# H0FR7.net
KiCad netlist of a schematic drawn in EAGLE
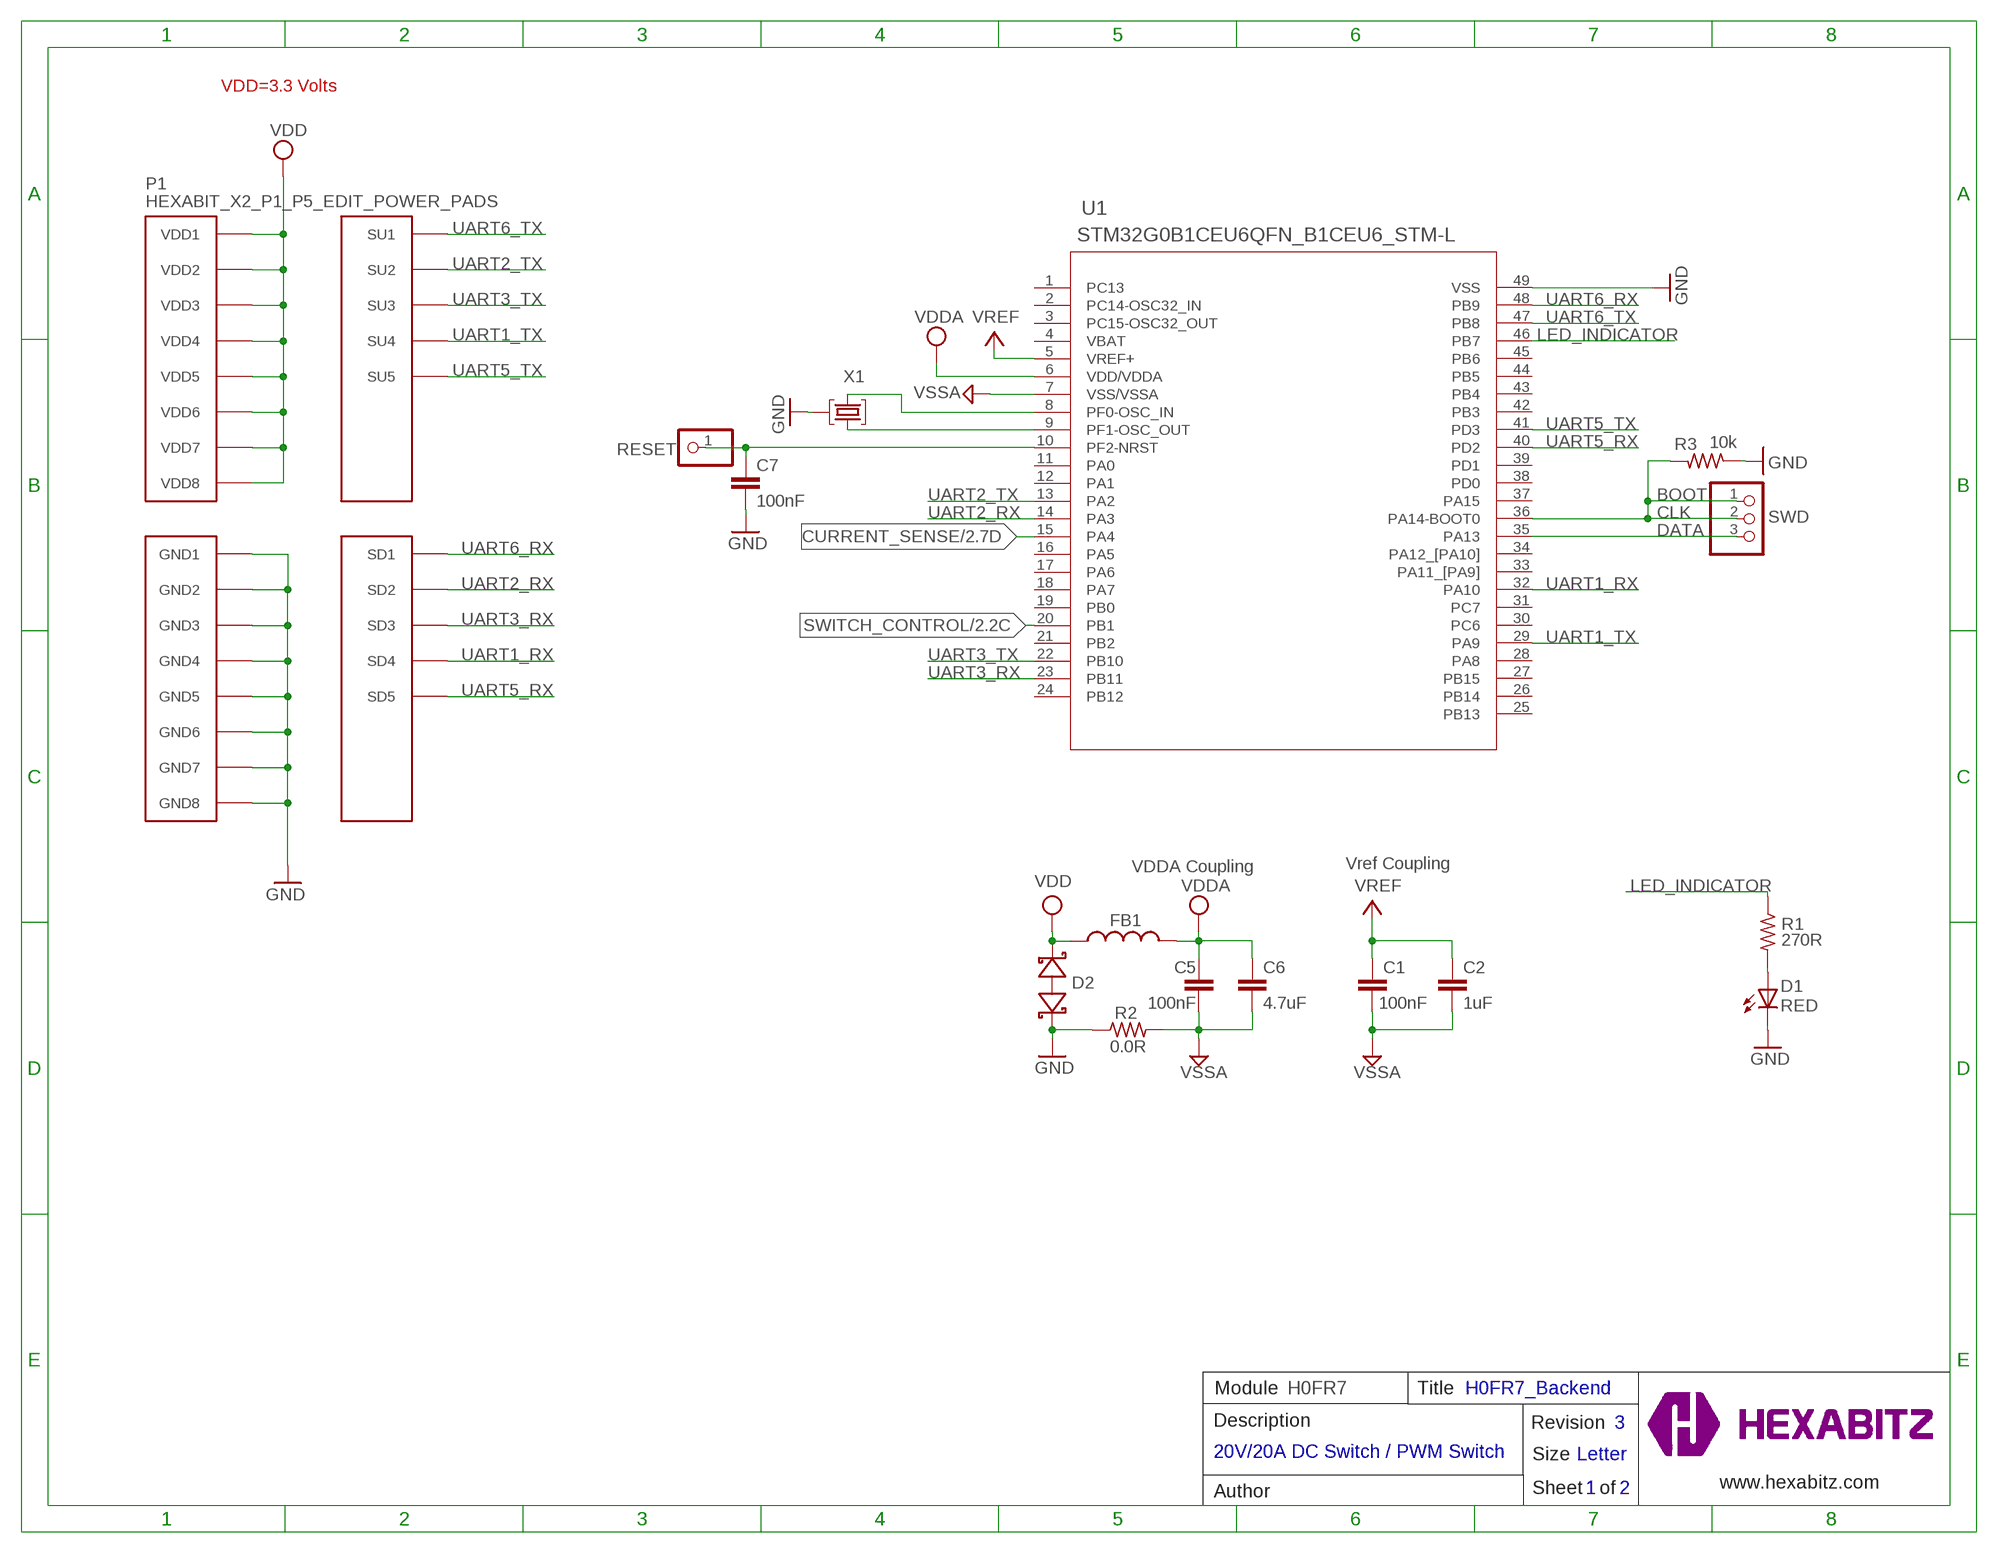
[diagram p0: schematic, sheet 1]
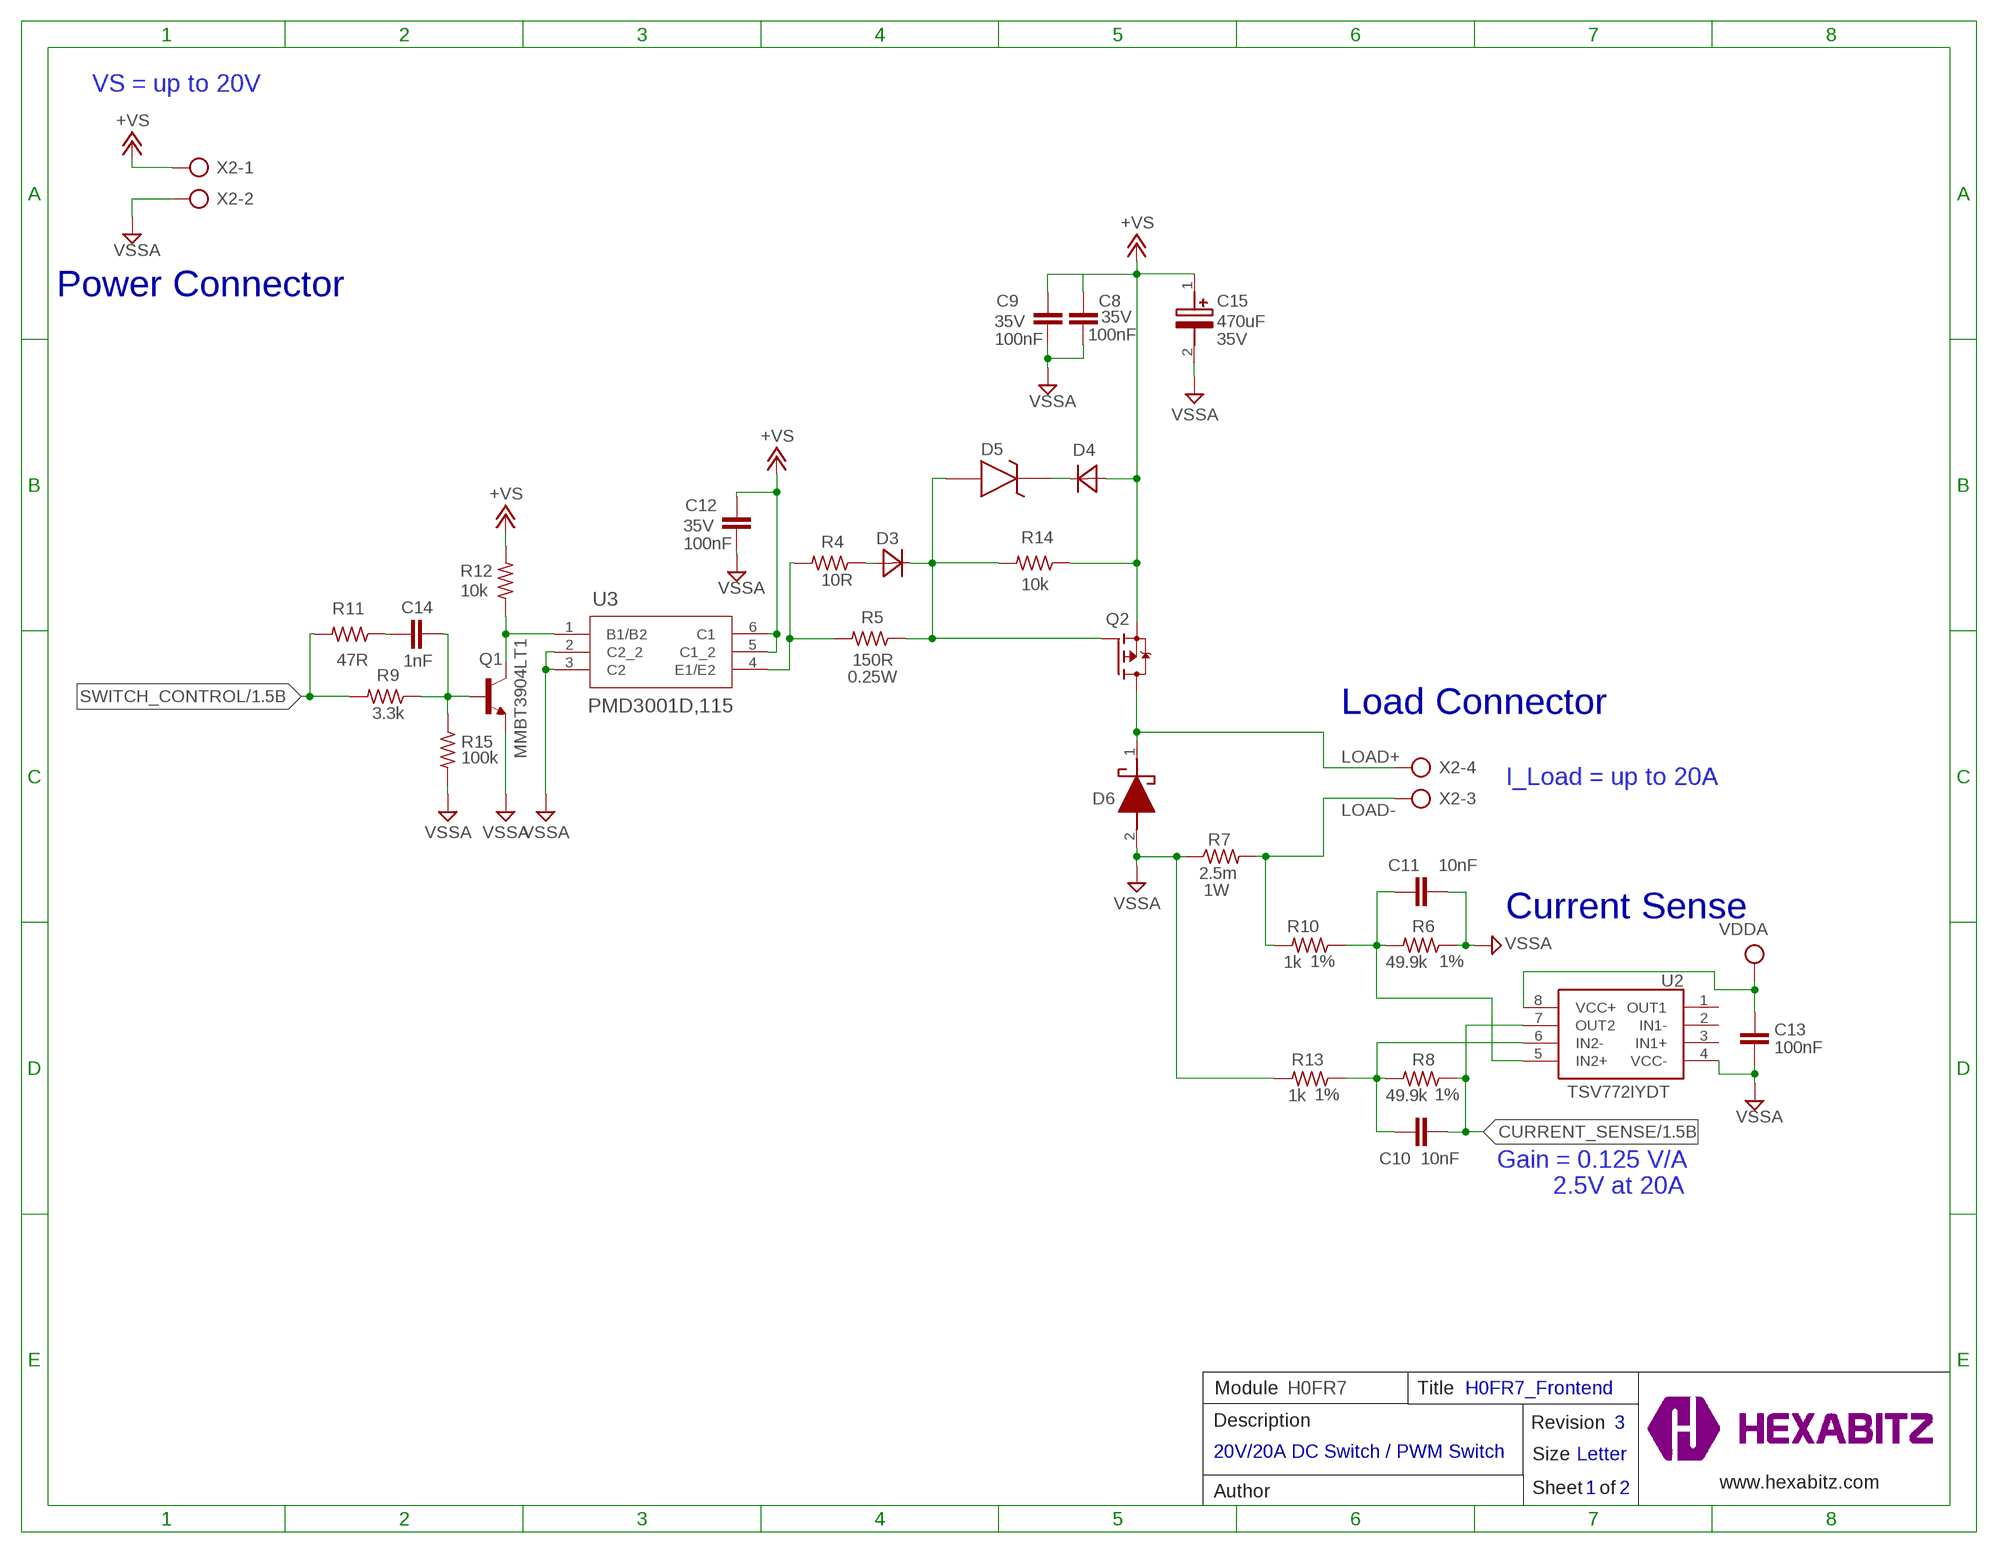
[diagram p1: schematic, sheet 2]

(export (version "E")
  (design (tool "Eeschema 10.0.6"))
  (components
    (comp (ref "C8")
      (value "C-0603")
      (footprint "eagle-import:C-0603")
      (fields (field (name "CAPACITANCE") "100nF") (field (name "VOLTAGE_RATING") "35V"))
      (libsource (lib "eagle-import") (part "C-0603"))
    )
    (comp (ref "C9")
      (value "C-0603")
      (footprint "eagle-import:C-0603")
      (fields (field (name "CAPACITANCE") "100nF") (field (name "VOLTAGE_RATING") "35V"))
      (libsource (lib "eagle-import") (part "C-0603"))
    )
    (comp (ref "C10")
      (value "10nF")
      (footprint "eagle-import:C-0603")
      (fields
        (field (name "CAPACITANCE") "100nF")
        (field (name "MFN") "KEMET")
        (field (name "MPN") "C0603C104K8RACTU")
        (field (name "OCTOPART_URL") "https://octopart.com/c0603c104k8ractu-kemet-145075?r=sp&s=9bS9ASSwSEqMCE9KBEQZ0g")
        (field (name "TOLERANCE") "10V")
        (field (name "VOLTAGE_RATING") "10%")
      )
      (libsource (lib "eagle-import") (part "C-0603"))
    )
    (comp (ref "C11")
      (value "10nF")
      (footprint "eagle-import:C-0603")
      (fields
        (field (name "CAPACITANCE") "100nF")
        (field (name "MFN") "KEMET")
        (field (name "MPN") "C0603C104K8RACTU")
        (field (name "OCTOPART_URL") "https://octopart.com/c0603c104k8ractu-kemet-145075?r=sp&s=9bS9ASSwSEqMCE9KBEQZ0g")
        (field (name "TOLERANCE") "10V")
        (field (name "VOLTAGE_RATING") "10%")
      )
      (libsource (lib "eagle-import") (part "C-0603"))
    )
    (comp (ref "C12")
      (value "C-0603")
      (footprint "eagle-import:C-0603")
      (fields (field (name "CAPACITANCE") "100nF") (field (name "VOLTAGE_RATING") "35V"))
      (libsource (lib "eagle-import") (part "C-0603"))
    )
    (comp (ref "C13")
      (value "100nF")
      (footprint "eagle-import:C-0603")
      (fields
        (field (name "CAPACITANCE") "100nF")
        (field (name "MFN") "KEMET")
        (field (name "MPN") "C0603C104K8RACTU")
        (field (name "OCTOPART_URL") "https://octopart.com/c0603c104k8ractu-kemet-145075?r=sp&s=9bS9ASSwSEqMCE9KBEQZ0g")
        (field (name "TOLERANCE") "10V")
        (field (name "VOLTAGE_RATING") "10%")
      )
      (libsource (lib "eagle-import") (part "C-0603"))
    )
    (comp (ref "C14")
      (value "1nF")
      (footprint "eagle-import:C-0603")
      (fields
        (field (name "CAPACITANCE") "100nF")
        (field (name "MFN") "KEMET")
        (field (name "MPN") "C0603C104K8RACTU")
        (field (name "OCTOPART_URL") "https://octopart.com/c0603c104k8ractu-kemet-145075?r=sp&s=9bS9ASSwSEqMCE9KBEQZ0g")
        (field (name "TOLERANCE") "10%")
        (field (name "VOLTAGE_RATING") "10V")
      )
      (libsource (lib "eagle-import") (part "C-0603"))
    )
    (comp (ref "C15")
      (value "ESH477M035AH3AA")
      (footprint "eagle-import:CAPPRD500W60D1000H1700")
      (fields
        (field (name "MOUSER_PART_NUMBER") "80-ESH477M035AH3AA")
        (field (name "CAPACITANCE") "470uF")
        (field (name "VOLT_RATING") "35V")
      )
      (libsource (lib "eagle-import") (part "ESH477M035AH3AA"))
    )
    (comp (ref "D3")
      (value "DIOD-SOD-123")
      (footprint "eagle-import:SOD123")
      (fields (field (name "MPN") "1N4148W-7-F"))
      (libsource (lib "eagle-import") (part "DIOD-SOD-123"))
    )
    (comp (ref "D4")
      (value "DIOD-SOD-123")
      (footprint "eagle-import:SOD123")
      (fields (field (name "MPN") "1N4148W-7-F"))
      (libsource (lib "eagle-import") (part "DIOD-SOD-123"))
    )
    (comp (ref "D5")
      (value "MMSZ4705T1GMMSZ4705T1G")
      (footprint "eagle-import:DIO_MMSZ4700T1G")
      (fields (field (name "MPN") "MMSZ4678T1G") (field (name "VOLTAGE") "18V"))
      (libsource (lib "eagle-import") (part "MMSZ4705T1GMMSZ4705T1G"))
    )
    (comp (ref "D6")
      (value "V8PAM10S-M3_H")
      (footprint "eagle-import:V8PAM10SHM3H")
      (fields
        (field (name "MANUFACTURER_PART_NUMBER") "V8PAM10S-M3/H")
        (field (name "MOUSER_PART_NUMBER") "78-V8PAM10S-M3/H")
      )
      (libsource (lib "eagle-import") (part "V8PAM10S-M3_H"))
    )
    (comp (ref "Q1")
      (value "MMBT3904LT1")
      (footprint "eagle-import:MMBT3904LT1")
      (libsource (lib "eagle-import") (part "MMBT3904LT1"))
    )
    (comp (ref "Q2")
      (value "STD36P4LLF6")
      (footprint "eagle-import:DPAK-3")
      (libsource (lib "eagle-import") (part "STD36P4LLF6"))
    )
    (comp (ref "R4")
      (value "10R")
      (footprint "eagle-import:R-0603")
      (fields
        (field (name "MFN") "Yageo")
        (field (name "MPN") "RC0603JR-07680KL")
        (field (name "OCTOPART_URL") "https://octopart.com/rc0603jr-07680kl-yageo-40953169?r=sp")
        (field (name "RESISTANCE") "680K Ohm")
        (field (name "TOLERANCE") "5%")
      )
      (libsource (lib "eagle-import") (part "R-0603"))
    )
    (comp (ref "R5")
      (value "150R")
      (footprint "eagle-import:R-0603")
      (fields (field (name "MPN") "CRGP0603F150R") (field (name "POWER") "0.25W"))
      (libsource (lib "eagle-import") (part "R-0603"))
    )
    (comp (ref "R6")
      (value "49.9k")
      (footprint "eagle-import:R-0603")
      (fields
        (field (name "MFN") "Yageo")
        (field (name "MPN") "RC0603JR-071KL")
        (field (name "OCTOPART_URL") "https://octopart.com/rc0603jr-071kl-yageo-55402888?r=sp")
        (field (name "RESISTANCE") "1k")
        (field (name "TOLERANCE") "1%")
      )
      (libsource (lib "eagle-import") (part "R-0603"))
    )
    (comp (ref "R7")
      (value "2.5m")
      (footprint "eagle-import:R1206")
      (fields
        (field (name "MPN") "RNCF2512BTE1M10")
        (field (name "MPN_1") "PA1206FRE472U5Z")
        (field (name "POWER") "1W")
      )
      (libsource (lib "eagle-import") (part "R_1206R1206"))
    )
    (comp (ref "R8")
      (value "49.9k")
      (footprint "eagle-import:R-0603")
      (fields
        (field (name "MFN") "Yageo")
        (field (name "MPN") "RC0603JR-071KL")
        (field (name "OCTOPART_URL") "https://octopart.com/rc0603jr-071kl-yageo-55402888?r=sp")
        (field (name "RESISTANCE") "1k")
        (field (name "TOLERANCE") "1%")
      )
      (libsource (lib "eagle-import") (part "R-0603"))
    )
    (comp (ref "R9")
      (value "3.3k")
      (footprint "eagle-import:R-0603")
      (fields
        (field (name "MFN") "Yageo")
        (field (name "MPN") "RC0603JR-07680KL")
        (field (name "OCTOPART_URL") "https://octopart.com/rc0603jr-07680kl-yageo-40953169?r=sp")
        (field (name "RESISTANCE") "680K Ohm")
        (field (name "TOLERANCE") "5%")
      )
      (libsource (lib "eagle-import") (part "R-0603"))
    )
    (comp (ref "R10")
      (value "1k")
      (footprint "eagle-import:R-0603")
      (fields
        (field (name "MFN") "Yageo")
        (field (name "MPN") "RC0603JR-071KL")
        (field (name "OCTOPART_URL") "https://octopart.com/rc0603jr-071kl-yageo-55402888?r=sp")
        (field (name "RESISTANCE") "1k")
        (field (name "TOLERANCE") "1%")
      )
      (libsource (lib "eagle-import") (part "R-0603"))
    )
    (comp (ref "R11")
      (value "47R")
      (footprint "eagle-import:R-0603")
      (fields
        (field (name "MFN") "Yageo")
        (field (name "MPN") "RC0603JR-07680KL")
        (field (name "OCTOPART_URL") "https://octopart.com/rc0603jr-07680kl-yageo-40953169?r=sp")
        (field (name "RESISTANCE") "680K Ohm")
        (field (name "TOLERANCE") "5%")
      )
      (libsource (lib "eagle-import") (part "R-0603"))
    )
    (comp (ref "R12")
      (value "10k")
      (footprint "eagle-import:R-0603")
      (fields
        (field (name "MFN") "Yageo")
        (field (name "MPN") "RC0603JR-0710KL")
        (field (name "OCTOPART_URL") "https://octopart.com/search?q=RC0603JR-0710KL&start=0")
        (field (name "RESISTANCE") "10.0K Ohm")
        (field (name "TOLERANCE") "5%")
      )
      (libsource (lib "eagle-import") (part "R-0603"))
    )
    (comp (ref "R13")
      (value "1k")
      (footprint "eagle-import:R-0603")
      (fields
        (field (name "MFN") "Yageo")
        (field (name "MPN") "RC0603JR-071KL")
        (field (name "OCTOPART_URL") "https://octopart.com/rc0603jr-071kl-yageo-55402888?r=sp")
        (field (name "RESISTANCE") "1k")
        (field (name "TOLERANCE") "1%")
      )
      (libsource (lib "eagle-import") (part "R-0603"))
    )
    (comp (ref "R14")
      (value "10k")
      (footprint "eagle-import:R-0603")
      (fields
        (field (name "MFN") "Yageo")
        (field (name "MPN") "RC0603JR-07680KL")
        (field (name "OCTOPART_URL") "https://octopart.com/rc0603jr-07680kl-yageo-40953169?r=sp")
        (field (name "RESISTANCE") "680K Ohm")
        (field (name "TOLERANCE") "5%")
      )
      (libsource (lib "eagle-import") (part "R-0603"))
    )
    (comp (ref "R15")
      (value "100k")
      (footprint "eagle-import:R-0603")
      (fields
        (field (name "MFN") "Yageo")
        (field (name "MPN") "RC0603JR-07680KL")
        (field (name "OCTOPART_URL") "https://octopart.com/rc0603jr-07680kl-yageo-40953169?r=sp")
        (field (name "RESISTANCE") "680K Ohm")
        (field (name "TOLERANCE") "5%")
      )
      (libsource (lib "eagle-import") (part "R-0603"))
    )
    (comp (ref "U2")
      (value "TSV772IYDT")
      (footprint "eagle-import:SOIC127P600X175-8N")
      (libsource (lib "eagle-import") (part "TSV772IYDT"))
    )
    (comp (ref "U3")
      (value "PMD3001D,115")
      (footprint "eagle-import:SOT457_NEX")
      (fields
        (field (name "MANUFACTURER_PART_NUMBER") "PMD3001D")
        (field (name "COPYRIGHT") "Copyright (C) 2022 Ultra Librarian. All rights reserved.")
      )
      (libsource (lib "eagle-import") (part "PMD3001DSOT457_NEX"))
    )
    (comp (ref "X2")
      (value "AK300/4")
      (footprint "eagle-import:AK300_4")
      (libsource (lib "eagle-import") (part "AK300/4"))
    )
    (comp (ref "C1")
      (value "100nF")
      (footprint "eagle-import:C-0603")
      (fields
        (field (name "CAPACITANCE") "100nF")
        (field (name "MFN") "KEMET")
        (field (name "MPN") "C0603C104K8RACTU")
        (field (name "OCTOPART_URL") "https://octopart.com/c0603c104k8ractu-kemet-145075?r=sp&s=9bS9ASSwSEqMCE9KBEQZ0g")
        (field (name "TOLERANCE") "10%")
        (field (name "VOLTAGE_RATING") "10V")
      )
      (libsource (lib "eagle-import") (part "C-0603"))
    )
    (comp (ref "C2")
      (value "1uF")
      (footprint "eagle-import:C-0805")
      (libsource (lib "eagle-import") (part "C-0805"))
    )
    (comp (ref "C5")
      (value "100nF")
      (footprint "eagle-import:C-0603")
      (libsource (lib "eagle-import") (part "C-0603"))
    )
    (comp (ref "C6")
      (value "4.7uF")
      (footprint "eagle-import:C-0805")
      (libsource (lib "eagle-import") (part "C-0805"))
    )
    (comp (ref "C7")
      (value "100nF")
      (footprint "eagle-import:C-0603")
      (fields
        (field (name "CAPACITANCE") "100nF")
        (field (name "MFN") "KEMET")
        (field (name "MPN") "C0603C104K8RACTU")
        (field (name "OCTOPART_URL") "https://octopart.com/c0603c104k8ractu-kemet-145075?r=sp&s=9bS9ASSwSEqMCE9KBEQZ0g")
        (field (name "TOLERANCE") "10%")
        (field (name "VOLTAGE_RATING") "10V")
      )
      (libsource (lib "eagle-import") (part "C-0603"))
    )
    (comp (ref "D1")
      (value "RED")
      (footprint "eagle-import:VLMS1300-GS08")
      (fields
        (field (name "MPN") "VLMS1300-GS08")
        (field (name "MFN") "Vishay")
        (field (name "MPN_1") "VLMS1300-GS08")
        (field (name "OCTOPART_URL") "https://octopart.com/vlms1300-gs08-vishay-21709201?r=sp&s=_gcP4_q8T1SC6PJQPTQ9yA")
      )
      (libsource (lib "eagle-import") (part "VLMS1300-GS08"))
    )
    (comp (ref "D2")
      (value "BOURNS_CDSOD323-T03SCBOURNS_CDSOD323-T03SC_0_0")
      (footprint "eagle-import:BOURNS_CDSOD323-T03SC_0")
      (fields (field (name "MPN") "CDSOD323-T03SC"))
      (libsource (lib "eagle-import") (part "BOURNS_CDSOD323-T03SCBOURNS_CDSOD323-T03SC_0_0"))
    )
    (comp (ref "FB1")
      (value "FB-0603")
      (footprint "eagle-import:FB-0603")
      (libsource (lib "eagle-import") (part "FB-0603"))
    )
    (comp (ref "P1")
      (value "HEXABIT_X2_P1_P5_EDIT_POWER_PADS")
      (footprint "eagle-import:HEXABIT_X2_P1_P5_EDIT_POWER_PADS")
      (libsource (lib "eagle-import") (part "HEXABIT_X2_P1_P5_EDIT_POWER_PADS"))
    )
    (comp (ref "R1")
      (value "270R")
      (footprint "eagle-import:R-0603")
      (libsource (lib "eagle-import") (part "R-0603"))
    )
    (comp (ref "R2")
      (value "0.0R")
      (footprint "eagle-import:R-0603")
      (libsource (lib "eagle-import") (part "R-0603"))
    )
    (comp (ref "R3")
      (value "10k")
      (footprint "eagle-import:R-0603")
      (fields
        (field (name "MFN") "Yageo")
        (field (name "MPN") "RC0603JR-0710KL")
        (field (name "OCTOPART_URL") "https://octopart.com/search?q=RC0603JR-0710KL&start=0")
        (field (name "RESISTANCE") "10.0K Ohm")
        (field (name "TOLERANCE") "5%")
      )
      (libsource (lib "eagle-import") (part "R-0603"))
    )
    (comp (ref "RESET")
      (value "R")
      (footprint "eagle-import:1X01")
      (fields (field (name "MPN") "87227-1"))
      (libsource (lib "eagle-import") (part "PINHD-1X1"))
    )
    (comp (ref "SWD")
      (value "PINHD-1X3SWD")
      (footprint "eagle-import:SWD")
      (libsource (lib "eagle-import") (part "PINHD-1X3SWD"))
    )
    (comp (ref "TRIMBLE-LOGO2")
      (value "HEXA-LOGO")
      (footprint "eagle-import:HEXA-LOGO")
      (libsource (lib "eagle-import") (part "HEXA-LOGO"))
    )
    (comp (ref "U1")
      (value "STM32G0B1CEU6QFN_B1CEU6_STM-L")
      (footprint "eagle-import:QFN_B1CEU6_STM-L")
      (fields
        (field (name "MANUFACTURER_PART_NUMBER") "STM32G0B1CEU6")
        (field (name "COPYRIGHT") "Copyright (C) 2021 Ultra Librarian. All rights reserved.")
      )
      (libsource (lib "eagle-import") (part "STM32G0B1CEU6QFN_B1CEU6_STM-L"))
    )
    (comp (ref "X1")
      (value "XTALL_CSTCE8M00G52")
      (footprint "eagle-import:XTALL_CSTCE8M00G52")
      (fields (field (name "MPN") "CSTCE8M00G52Z-R0"))
      (libsource (lib "eagle-import") (part "XTALL_CSTCE8M00G52"))
    )
  )
  (nets
    (net (code "1") (name "+VS") (class "Default")
      (node (ref "C12") (pin "2") (pinfunction "2_2") (pintype "passive"))
      (node (ref "C15") (pin "1") (pinfunction "+_1") (pintype "bidirectional"))
      (node (ref "C8") (pin "2") (pinfunction "2_2") (pintype "passive"))
      (node (ref "C9") (pin "2") (pinfunction "2_2") (pintype "passive"))
      (node (ref "D4") (pin "1") (pinfunction "A_1") (pintype "passive"))
      (node (ref "Q2") (pin "3") (pinfunction "S_3") (pintype "passive"))
      (node (ref "R12") (pin "2") (pinfunction "2_2") (pintype "passive"))
      (node (ref "R14") (pin "1") (pinfunction "1_1") (pintype "passive"))
      (node (ref "U3") (pin "5") (pinfunction "C1_2_5") (pintype "passive"))
      (node (ref "U3") (pin "6") (pinfunction "C1_6") (pintype "passive"))
      (node (ref "X2") (pin "1") (pinfunction "KL_1") (pintype "passive"))
    )
    (net (code "2") (name "CLK") (class "Default")
      (node (ref "R3") (pin "2") (pinfunction "2_2") (pintype "passive"))
      (node (ref "SWD") (pin "1") (pinfunction "1_1") (pintype "passive"))
      (node (ref "SWD") (pin "2") (pinfunction "2_2") (pintype "passive"))
      (node (ref "U1") (pin "36") (pinfunction "PA14-BOOT0_36") (pintype "bidirectional"))
    )
    (net (code "3") (name "CURRENT_SENSE") (class "Default")
      (node (ref "C10") (pin "2") (pinfunction "2_2") (pintype "passive"))
      (node (ref "R8") (pin "1") (pinfunction "1_1") (pintype "passive"))
      (node (ref "U1") (pin "15") (pinfunction "PA4_15") (pintype "bidirectional"))
      (node (ref "U2") (pin "7") (pinfunction "OUT2_7") (pintype "bidirectional"))
    )
    (net (code "4") (name "DATA") (class "Default")
      (node (ref "SWD") (pin "3") (pinfunction "3_3") (pintype "passive"))
      (node (ref "U1") (pin "35") (pinfunction "PA13_35") (pintype "bidirectional"))
    )
    (net (code "5") (name "GND") (class "Default")
      (node (ref "C7") (pin "2") (pinfunction "2_2") (pintype "passive"))
      (node (ref "D1") (pin "C") (pinfunction "C_C") (pintype "passive"))
      (node (ref "D2") (pin "2") (pinfunction "C_2") (pintype "passive"))
      (node (ref "P1") (pin "PAD_PD11") (pinfunction "GND1_PAD_PD11") (pintype "power_in"))
      (node (ref "P1") (pin "PAD_PD12") (pinfunction "GND2_PAD_PD12") (pintype "power_in"))
      (node (ref "P1") (pin "PAD_PD13") (pinfunction "GND3_PAD_PD13") (pintype "power_in"))
      (node (ref "P1") (pin "PAD_PD14") (pinfunction "GND4_PAD_PD14") (pintype "power_in"))
      (node (ref "P1") (pin "PAD_PD17") (pinfunction "GND5_PAD_PD17") (pintype "power_in"))
      (node (ref "P1") (pin "PAD_PD18") (pinfunction "GND6_PAD_PD18") (pintype "power_in"))
      (node (ref "P1") (pin "PAD_PD19") (pinfunction "GND7_PAD_PD19") (pintype "power_in"))
      (node (ref "P1") (pin "PAD_PD20") (pinfunction "GND8_PAD_PD20") (pintype "power_in"))
      (node (ref "R2") (pin "1") (pinfunction "1_1") (pintype "passive"))
      (node (ref "R3") (pin "1") (pinfunction "1_1") (pintype "passive"))
      (node (ref "U1") (pin "49") (pinfunction "VSS_49") (pintype "passive"))
      (node (ref "X1") (pin "P$2") (pinfunction "2_P$2") (pintype "passive"))
    )
    (net (code "6") (name "LED_INDICATOR") (class "Default")
      (node (ref "R1") (pin "1") (pinfunction "1_1") (pintype "passive"))
      (node (ref "U1") (pin "46") (pinfunction "PB7_46") (pintype "bidirectional"))
    )
    (net (code "7") (name "LOAD+") (class "Default")
      (node (ref "D6") (pin "1") (pinfunction "K_1") (pintype "bidirectional"))
      (node (ref "Q2") (pin "4") (pinfunction "D_4") (pintype "passive"))
      (node (ref "X2") (pin "4") (pinfunction "KL_4") (pintype "passive"))
    )
    (net (code "8") (name "LOAD-") (class "Default")
      (node (ref "R10") (pin "2") (pinfunction "2_2") (pintype "passive"))
      (node (ref "R7") (pin "2") (pinfunction "2_2") (pintype "passive"))
      (node (ref "X2") (pin "3") (pinfunction "KL_3") (pintype "passive"))
    )
    (net (code "9") (name "Net-(C14-Pad1)") (class "Default")
      (node (ref "C14") (pin "1") (pinfunction "1_1") (pintype "passive"))
      (node (ref "R11") (pin "1") (pinfunction "1_1") (pintype "passive"))
    )
    (net (code "10") (name "Net-(D1-PadA)") (class "Default")
      (node (ref "D1") (pin "A") (pinfunction "A_A") (pintype "passive"))
      (node (ref "R1") (pin "2") (pinfunction "2_2") (pintype "passive"))
    )
    (net (code "11") (name "Net-(D3-A)") (class "Default")
      (node (ref "D3") (pin "1") (pinfunction "A_1") (pintype "passive"))
      (node (ref "R4") (pin "1") (pinfunction "1_1") (pintype "passive"))
    )
    (net (code "12") (name "Net-(D3-C)") (class "Default")
      (node (ref "D3") (pin "2") (pinfunction "C_2") (pintype "passive"))
      (node (ref "D5") (pin "A") (pinfunction "A_A") (pintype "bidirectional"))
      (node (ref "Q2") (pin "1") (pinfunction "G_1") (pintype "passive"))
      (node (ref "R14") (pin "2") (pinfunction "2_2") (pintype "passive"))
      (node (ref "R5") (pin "1") (pinfunction "1_1") (pintype "passive"))
    )
    (net (code "13") (name "Net-(D4-C)") (class "Default")
      (node (ref "D4") (pin "2") (pinfunction "C_2") (pintype "passive"))
      (node (ref "D5") (pin "K") (pinfunction "K_K") (pintype "bidirectional"))
    )
    (net (code "14") (name "Net-(Q1-B)") (class "Default")
      (node (ref "C14") (pin "2") (pinfunction "2_2") (pintype "passive"))
      (node (ref "Q1") (pin "1") (pinfunction "B_1") (pintype "passive"))
      (node (ref "R15") (pin "1") (pinfunction "1_1") (pintype "passive"))
      (node (ref "R9") (pin "1") (pinfunction "1_1") (pintype "passive"))
    )
    (net (code "15") (name "Net-(Q1-C)") (class "Default")
      (node (ref "Q1") (pin "3") (pinfunction "C_3") (pintype "passive"))
      (node (ref "R12") (pin "1") (pinfunction "1_1") (pintype "passive"))
      (node (ref "U3") (pin "1") (pinfunction "B1/B2_1") (pintype "passive"))
    )
    (net (code "16") (name "Net-(U1-PF0-OSC_IN)") (class "Default")
      (node (ref "U1") (pin "8") (pinfunction "PF0-OSC_IN_8") (pintype "bidirectional"))
      (node (ref "X1") (pin "P$1") (pinfunction "1_P$1") (pintype "passive"))
    )
    (net (code "17") (name "Net-(U1-PF1-OSC_OUT)") (class "Default")
      (node (ref "U1") (pin "9") (pinfunction "PF1-OSC_OUT_9") (pintype "output"))
      (node (ref "X1") (pin "P$3") (pinfunction "3_P$3") (pintype "passive"))
    )
    (net (code "18") (name "Net-(U1-PF2-NRST)") (class "Default")
      (node (ref "C7") (pin "1") (pinfunction "1_1") (pintype "passive"))
      (node (ref "RESET") (pin "1") (pinfunction "1_1") (pintype "passive"))
      (node (ref "U1") (pin "10") (pinfunction "PF2-NRST_10") (pintype "bidirectional"))
    )
    (net (code "19") (name "Net-(U2-IN2+)") (class "Default")
      (node (ref "C11") (pin "1") (pinfunction "1_1") (pintype "passive"))
      (node (ref "R10") (pin "1") (pinfunction "1_1") (pintype "passive"))
      (node (ref "R6") (pin "2") (pinfunction "2_2") (pintype "passive"))
      (node (ref "U2") (pin "5") (pinfunction "IN2+_5") (pintype "bidirectional"))
    )
    (net (code "20") (name "Net-(U2-IN2-)") (class "Default")
      (node (ref "C10") (pin "1") (pinfunction "1_1") (pintype "passive"))
      (node (ref "R13") (pin "1") (pinfunction "1_1") (pintype "passive"))
      (node (ref "R8") (pin "2") (pinfunction "2_2") (pintype "passive"))
      (node (ref "U2") (pin "6") (pinfunction "IN2-_6") (pintype "bidirectional"))
    )
    (net (code "21") (name "Net-(U3-E1{slash}E2)") (class "Default")
      (node (ref "R4") (pin "2") (pinfunction "2_2") (pintype "passive"))
      (node (ref "R5") (pin "2") (pinfunction "2_2") (pintype "passive"))
      (node (ref "U3") (pin "4") (pinfunction "E1/E2_4") (pintype "passive"))
    )
    (net (code "22") (name "SWITCH_CONTROL") (class "Default")
      (node (ref "R11") (pin "2") (pinfunction "2_2") (pintype "passive"))
      (node (ref "R9") (pin "2") (pinfunction "2_2") (pintype "passive"))
      (node (ref "U1") (pin "20") (pinfunction "PB1_20") (pintype "bidirectional"))
    )
    (net (code "23") (name "UART1_RX") (class "Default")
      (node (ref "P1") (pin "PAD_PD4") (pinfunction "SD4_PAD_PD4") (pintype "bidirectional"))
      (node (ref "U1") (pin "32") (pinfunction "PA10_32") (pintype "bidirectional"))
    )
    (net (code "24") (name "UART1_TX") (class "Default")
      (node (ref "P1") (pin "PAD_PU4") (pinfunction "SU4_PAD_PU4") (pintype "bidirectional"))
      (node (ref "U1") (pin "29") (pinfunction "PA9_29") (pintype "bidirectional"))
    )
    (net (code "25") (name "UART2_RX") (class "Default")
      (node (ref "P1") (pin "PAD_PD2") (pinfunction "SD2_PAD_PD2") (pintype "bidirectional"))
      (node (ref "U1") (pin "14") (pinfunction "PA3_14") (pintype "bidirectional"))
    )
    (net (code "26") (name "UART2_TX") (class "Default")
      (node (ref "P1") (pin "PAD_PU2") (pinfunction "SU2_PAD_PU2") (pintype "bidirectional"))
      (node (ref "U1") (pin "13") (pinfunction "PA2_13") (pintype "bidirectional"))
    )
    (net (code "27") (name "UART3_RX") (class "Default")
      (node (ref "P1") (pin "PAD_PD3") (pinfunction "SD3_PAD_PD3") (pintype "bidirectional"))
      (node (ref "U1") (pin "23") (pinfunction "PB11_23") (pintype "bidirectional"))
    )
    (net (code "28") (name "UART3_TX") (class "Default")
      (node (ref "P1") (pin "PAD_PU3") (pinfunction "SU3_PAD_PU3") (pintype "bidirectional"))
      (node (ref "U1") (pin "22") (pinfunction "PB10_22") (pintype "bidirectional"))
    )
    (net (code "29") (name "UART5_RX") (class "Default")
      (node (ref "P1") (pin "PAD_PD5") (pinfunction "SD5_PAD_PD5") (pintype "bidirectional"))
      (node (ref "U1") (pin "40") (pinfunction "PD2_40") (pintype "bidirectional"))
    )
    (net (code "30") (name "UART5_TX") (class "Default")
      (node (ref "P1") (pin "PAD_PU5") (pinfunction "SU5_PAD_PU5") (pintype "bidirectional"))
      (node (ref "U1") (pin "41") (pinfunction "PD3_41") (pintype "bidirectional"))
    )
    (net (code "31") (name "UART6_RX") (class "Default")
      (node (ref "P1") (pin "PAD_PD1") (pinfunction "SD1_PAD_PD1") (pintype "bidirectional"))
      (node (ref "U1") (pin "48") (pinfunction "PB9_48") (pintype "bidirectional"))
    )
    (net (code "32") (name "UART6_TX") (class "Default")
      (node (ref "P1") (pin "PAD_PU1") (pinfunction "SU1_PAD_PU1") (pintype "bidirectional"))
      (node (ref "U1") (pin "47") (pinfunction "PB8_47") (pintype "bidirectional"))
    )
    (net (code "33") (name "VDD") (class "Default")
      (node (ref "D2") (pin "1") (pinfunction "A_1") (pintype "passive"))
      (node (ref "FB1") (pin "1") (pinfunction "1_1") (pintype "passive"))
      (node (ref "P1") (pin "PAD_PU11") (pinfunction "VDD1_PAD_PU11") (pintype "power_in"))
      (node (ref "P1") (pin "PAD_PU12") (pinfunction "VDD2_PAD_PU12") (pintype "power_in"))
      (node (ref "P1") (pin "PAD_PU13") (pinfunction "VDD3_PAD_PU13") (pintype "power_in"))
      (node (ref "P1") (pin "PAD_PU14") (pinfunction "VDD4_PAD_PU14") (pintype "power_in"))
      (node (ref "P1") (pin "PAD_PU17") (pinfunction "VDD5_PAD_PU17") (pintype "power_in"))
      (node (ref "P1") (pin "PAD_PU18") (pinfunction "VDD6_PAD_PU18") (pintype "power_in"))
      (node (ref "P1") (pin "PAD_PU19") (pinfunction "VDD7_PAD_PU19") (pintype "power_in"))
      (node (ref "P1") (pin "PAD_PU20") (pinfunction "VDD8_PAD_PU20") (pintype "power_in"))
    )
    (net (code "34") (name "VDDA") (class "Default")
      (node (ref "C13") (pin "2") (pinfunction "2_2") (pintype "passive"))
      (node (ref "C5") (pin "1") (pinfunction "1_1") (pintype "passive"))
      (node (ref "C6") (pin "1") (pinfunction "1_1") (pintype "passive"))
      (node (ref "FB1") (pin "2") (pinfunction "2_2") (pintype "passive"))
      (node (ref "U1") (pin "6") (pinfunction "VDD/VDDA_6") (pintype "power_in"))
      (node (ref "U2") (pin "8") (pinfunction "VCC+_8") (pintype "bidirectional"))
    )
    (net (code "35") (name "VREF") (class "Default")
      (node (ref "C1") (pin "1") (pinfunction "1_1") (pintype "passive"))
      (node (ref "C2") (pin "1") (pinfunction "1_1") (pintype "passive"))
      (node (ref "U1") (pin "5") (pinfunction "VREF+_5") (pintype "power_in"))
    )
    (net (code "36") (name "VSSA") (class "Default")
      (node (ref "C1") (pin "2") (pinfunction "2_2") (pintype "passive"))
      (node (ref "C11") (pin "2") (pinfunction "2_2") (pintype "passive"))
      (node (ref "C12") (pin "1") (pinfunction "1_1") (pintype "passive"))
      (node (ref "C13") (pin "1") (pinfunction "1_1") (pintype "passive"))
      (node (ref "C15") (pin "2") (pinfunction "-_2") (pintype "bidirectional"))
      (node (ref "C2") (pin "2") (pinfunction "2_2") (pintype "passive"))
      (node (ref "C5") (pin "2") (pinfunction "2_2") (pintype "passive"))
      (node (ref "C6") (pin "2") (pinfunction "2_2") (pintype "passive"))
      (node (ref "C8") (pin "1") (pinfunction "1_1") (pintype "passive"))
      (node (ref "C9") (pin "1") (pinfunction "1_1") (pintype "passive"))
      (node (ref "D6") (pin "2") (pinfunction "A_2") (pintype "bidirectional"))
      (node (ref "Q1") (pin "2") (pinfunction "E_2") (pintype "passive"))
      (node (ref "R13") (pin "2") (pinfunction "2_2") (pintype "passive"))
      (node (ref "R15") (pin "2") (pinfunction "2_2") (pintype "passive"))
      (node (ref "R2") (pin "2") (pinfunction "2_2") (pintype "passive"))
      (node (ref "R6") (pin "1") (pinfunction "1_1") (pintype "passive"))
      (node (ref "R7") (pin "1") (pinfunction "1_1") (pintype "passive"))
      (node (ref "U1") (pin "7") (pinfunction "VSS/VSSA_7") (pintype "passive"))
      (node (ref "U2") (pin "4") (pinfunction "VCC-_4") (pintype "bidirectional"))
      (node (ref "U3") (pin "2") (pinfunction "C2_2_2") (pintype "passive"))
      (node (ref "U3") (pin "3") (pinfunction "C2_3") (pintype "passive"))
      (node (ref "X2") (pin "2") (pinfunction "KL_2") (pintype "passive"))
    )
    (net (code "37") (name "unconnected-(U1-PA0-Pad11)") (class "Default")
      (node (ref "U1") (pin "11") (pinfunction "PA0_11") (pintype "bidirectional"))
    )
    (net (code "38") (name "unconnected-(U1-PA1-Pad12)") (class "Default")
      (node (ref "U1") (pin "12") (pinfunction "PA1_12") (pintype "bidirectional"))
    )
    (net (code "39") (name "unconnected-(U1-PA5-Pad16)") (class "Default")
      (node (ref "U1") (pin "16") (pinfunction "PA5_16") (pintype "bidirectional"))
    )
    (net (code "40") (name "unconnected-(U1-PA6-Pad17)") (class "Default")
      (node (ref "U1") (pin "17") (pinfunction "PA6_17") (pintype "bidirectional"))
    )
    (net (code "41") (name "unconnected-(U1-PA7-Pad18)") (class "Default")
      (node (ref "U1") (pin "18") (pinfunction "PA7_18") (pintype "bidirectional"))
    )
    (net (code "42") (name "unconnected-(U1-PA8-Pad28)") (class "Default")
      (node (ref "U1") (pin "28") (pinfunction "PA8_28") (pintype "bidirectional"))
    )
    (net (code "43") (name "unconnected-(U1-PA11_[PA9]-Pad33)") (class "Default")
      (node (ref "U1") (pin "33") (pinfunction "PA11_[PA9]_33") (pintype "bidirectional"))
    )
    (net (code "44") (name "unconnected-(U1-PA12_[PA10]-Pad34)") (class "Default")
      (node (ref "U1") (pin "34") (pinfunction "PA12_[PA10]_34") (pintype "bidirectional"))
    )
    (net (code "45") (name "unconnected-(U1-PA15-Pad37)") (class "Default")
      (node (ref "U1") (pin "37") (pinfunction "PA15_37") (pintype "bidirectional"))
    )
    (net (code "46") (name "unconnected-(U1-PB0-Pad19)") (class "Default")
      (node (ref "U1") (pin "19") (pinfunction "PB0_19") (pintype "bidirectional"))
    )
    (net (code "47") (name "unconnected-(U1-PB2-Pad21)") (class "Default")
      (node (ref "U1") (pin "21") (pinfunction "PB2_21") (pintype "bidirectional"))
    )
    (net (code "48") (name "unconnected-(U1-PB3-Pad42)") (class "Default")
      (node (ref "U1") (pin "42") (pinfunction "PB3_42") (pintype "bidirectional"))
    )
    (net (code "49") (name "unconnected-(U1-PB4-Pad43)") (class "Default")
      (node (ref "U1") (pin "43") (pinfunction "PB4_43") (pintype "bidirectional"))
    )
    (net (code "50") (name "unconnected-(U1-PB5-Pad44)") (class "Default")
      (node (ref "U1") (pin "44") (pinfunction "PB5_44") (pintype "bidirectional"))
    )
    (net (code "51") (name "unconnected-(U1-PB6-Pad45)") (class "Default")
      (node (ref "U1") (pin "45") (pinfunction "PB6_45") (pintype "bidirectional"))
    )
    (net (code "52") (name "unconnected-(U1-PB12-Pad24)") (class "Default")
      (node (ref "U1") (pin "24") (pinfunction "PB12_24") (pintype "bidirectional"))
    )
    (net (code "53") (name "unconnected-(U1-PB13-Pad25)") (class "Default")
      (node (ref "U1") (pin "25") (pinfunction "PB13_25") (pintype "bidirectional"))
    )
    (net (code "54") (name "unconnected-(U1-PB14-Pad26)") (class "Default")
      (node (ref "U1") (pin "26") (pinfunction "PB14_26") (pintype "bidirectional"))
    )
    (net (code "55") (name "unconnected-(U1-PB15-Pad27)") (class "Default")
      (node (ref "U1") (pin "27") (pinfunction "PB15_27") (pintype "bidirectional"))
    )
    (net (code "56") (name "unconnected-(U1-PC6-Pad30)") (class "Default")
      (node (ref "U1") (pin "30") (pinfunction "PC6_30") (pintype "bidirectional"))
    )
    (net (code "57") (name "unconnected-(U1-PC7-Pad31)") (class "Default")
      (node (ref "U1") (pin "31") (pinfunction "PC7_31") (pintype "bidirectional"))
    )
    (net (code "58") (name "unconnected-(U1-PC13-Pad1)") (class "Default")
      (node (ref "U1") (pin "1") (pinfunction "PC13_1") (pintype "bidirectional"))
    )
    (net (code "59") (name "unconnected-(U1-PC14-OSC32_IN-Pad2)") (class "Default")
      (node (ref "U1") (pin "2") (pinfunction "PC14-OSC32_IN_2") (pintype "bidirectional"))
    )
    (net (code "60") (name "unconnected-(U1-PC15-OSC32_OUT-Pad3)") (class "Default")
      (node (ref "U1") (pin "3") (pinfunction "PC15-OSC32_OUT_3") (pintype "output"))
    )
    (net (code "61") (name "unconnected-(U1-PD0-Pad38)") (class "Default")
      (node (ref "U1") (pin "38") (pinfunction "PD0_38") (pintype "bidirectional"))
    )
    (net (code "62") (name "unconnected-(U1-PD1-Pad39)") (class "Default")
      (node (ref "U1") (pin "39") (pinfunction "PD1_39") (pintype "bidirectional"))
    )
    (net (code "63") (name "unconnected-(U1-VBAT-Pad4)") (class "Default")
      (node (ref "U1") (pin "4") (pinfunction "VBAT_4") (pintype "passive"))
    )
    (net (code "64") (name "unconnected-(U2-IN1+-Pad3)") (class "Default")
      (node (ref "U2") (pin "3") (pinfunction "IN1+_3") (pintype "bidirectional"))
    )
    (net (code "65") (name "unconnected-(U2-IN1--Pad2)") (class "Default")
      (node (ref "U2") (pin "2") (pinfunction "IN1-_2") (pintype "bidirectional"))
    )
    (net (code "66") (name "unconnected-(U2-OUT1-Pad1)") (class "Default")
      (node (ref "U2") (pin "1") (pinfunction "OUT1_1") (pintype "bidirectional"))
    )
  )
)
